# design.net
KiCad netlist of a schematic drawn in Altium Designer
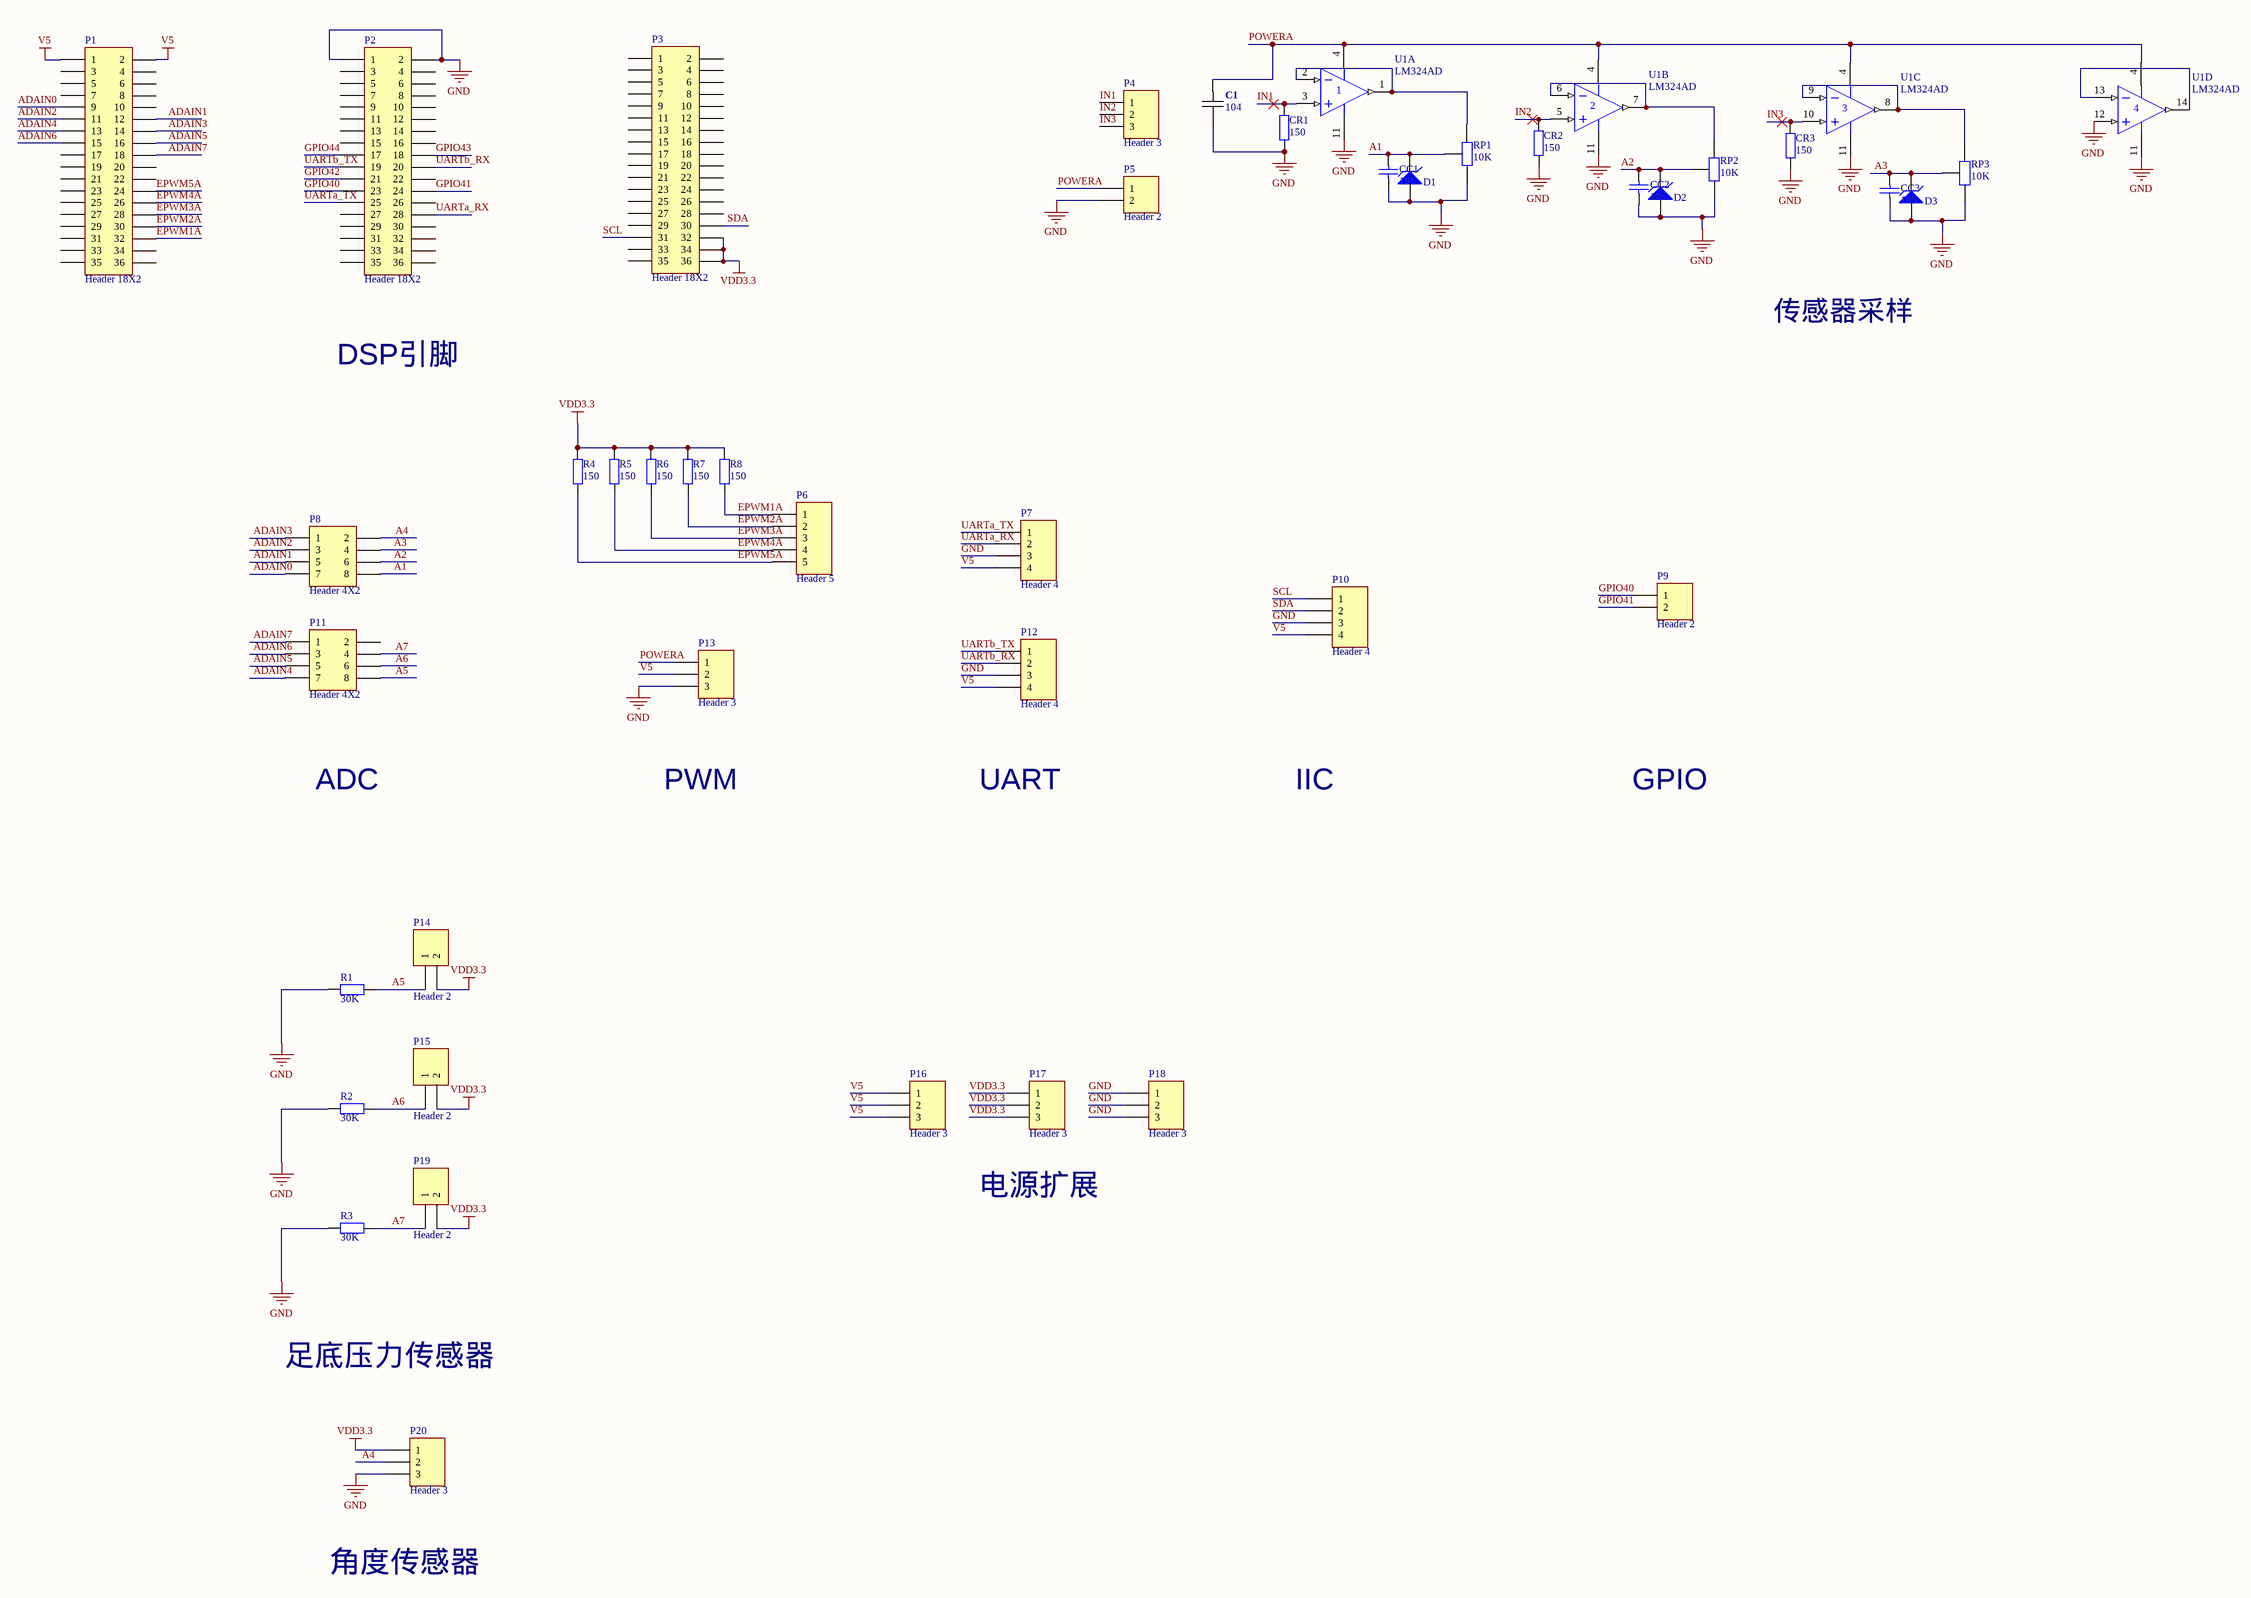
[diagram p0: 假肢控制电路.SchDoc]

(export (version "E")
  (design (tool "Eeschema 10.0.6"))
  (components
    (comp (ref "C1")
      (value "104")
      (footprint "LC-0805_C")
      (description "1.02.08.0014")
      (libsource (lib "电容(插装)") (part "CAP(瓷片,104)"))
    )
    (comp (ref "CC1")
      (value "105")
      (footprint "LC-0805_C")
      (description "Polarized Capacitor (Radial)")
      (fields (field (name "PUBLISHER") "Altium Limited"))
      (libsource (lib "主板") (part "Cap Chip 0805"))
    )
    (comp (ref "CC2")
      (value "105")
      (footprint "LC-0805_C")
      (description "Polarized Capacitor (Radial)")
      (fields (field (name "PUBLISHER") "Altium Limited"))
      (libsource (lib "主板") (part "Cap Chip 0805"))
    )
    (comp (ref "CC3")
      (value "105")
      (footprint "LC-0805_C")
      (description "Polarized Capacitor (Radial)")
      (fields (field (name "PUBLISHER") "Altium Limited"))
      (libsource (lib "主板") (part "Cap Chip 0805"))
    )
    (comp (ref "CR1")
      (value "150")
      (footprint "LC-0805_R")
      (description "Resistor")
      (fields (field (name "PUBLISHER") "Altium Limited"))
      (libsource (lib "主板") (part "Resistor Chip 0805"))
    )
    (comp (ref "CR2")
      (value "150")
      (footprint "LC-0805_R")
      (description "Resistor")
      (fields (field (name "PUBLISHER") "Altium Limited"))
      (libsource (lib "主板") (part "Resistor Chip 0805"))
    )
    (comp (ref "CR3")
      (value "150")
      (footprint "LC-0805_R")
      (description "Resistor")
      (fields (field (name "PUBLISHER") "Altium Limited"))
      (libsource (lib "主板") (part "Resistor Chip 0805"))
    )
    (comp (ref "D1")
      (value "Diode  Zener")
      (footprint "LC-1206")
      (description "Zener Diode")
      (fields (field (name "PUBLISHER") "Altium Limited"))
      (libsource (lib "EButterflyIntegratedLibrary") (part "Diode  Zener"))
    )
    (comp (ref "D2")
      (value "Diode  Zener")
      (footprint "LC-1206")
      (description "Zener Diode")
      (fields (field (name "PUBLISHER") "Altium Limited"))
      (libsource (lib "EButterflyIntegratedLibrary") (part "Diode  Zener"))
    )
    (comp (ref "D3")
      (value "Diode  Zener")
      (footprint "LC-1206")
      (description "Zener Diode")
      (fields (field (name "PUBLISHER") "Altium Limited"))
      (libsource (lib "EButterflyIntegratedLibrary") (part "Diode  Zener"))
    )
    (comp (ref "P1")
      (value "Header 18X2")
      (footprint "HDR2X18")
      (description "Header, 18-Pin, Dual row")
      (fields (field (name "PUBLISHER") "Altium Limited"))
      (libsource (lib "Miscellaneous Connectors") (part "Header 18X2"))
    )
    (comp (ref "P2")
      (value "Header 18X2")
      (footprint "HDR2X18")
      (description "Header, 18-Pin, Dual row")
      (fields (field (name "PUBLISHER") "Altium Limited"))
      (libsource (lib "Miscellaneous Connectors") (part "Header 18X2"))
    )
    (comp (ref "P3")
      (value "Header 18X2")
      (footprint "HDR2X18")
      (description "Header, 18-Pin, Dual row")
      (fields (field (name "PUBLISHER") "Altium Limited"))
      (libsource (lib "Miscellaneous Connectors") (part "Header 18X2"))
    )
    (comp (ref "P4")
      (value "Header 3")
      (footprint "XH2.54-3")
      (description "Header, 3-Pin")
      (fields (field (name "PUBLISHER") "Altium Limited"))
      (libsource (lib "Miscellaneous Connectors") (part "Header 3"))
    )
    (comp (ref "P5")
      (value "Header 2")
      (footprint "XH2.54-2")
      (description "Header, 2-Pin")
      (fields (field (name "PUBLISHER") "Altium Limited"))
      (libsource (lib "Miscellaneous Connectors") (part "Header 2"))
    )
    (comp (ref "P6")
      (value "Header 5")
      (footprint "XH2.54-LI-5P")
      (description "Header, 5-Pin")
      (fields (field (name "PUBLISHER") "Altium Limited"))
      (libsource (lib "Miscellaneous Connectors") (part "Header 5"))
    )
    (comp (ref "P7")
      (value "Header 4")
      (footprint "HDR1X4")
      (description "Header, 4-Pin")
      (fields (field (name "PUBLISHER") "Altium Limited"))
      (libsource (lib "Miscellaneous Connectors") (part "Header 4"))
    )
    (comp (ref "P8")
      (value "Header 4X2")
      (footprint "HDR2X4")
      (description "Header, 4-Pin, Dual row")
      (fields (field (name "PUBLISHER") "Altium Limited"))
      (libsource (lib "Miscellaneous Connectors") (part "Header 4X2"))
    )
    (comp (ref "P9")
      (value "Header 2")
      (footprint "HDR1X2")
      (description "Header, 2-Pin")
      (fields (field (name "PUBLISHER") "Altium Limited"))
      (libsource (lib "Miscellaneous Connectors") (part "Header 2"))
    )
    (comp (ref "P10")
      (value "Header 4")
      (footprint "KF接线端子:KF2EDGK5.0-LI-4P")
      (description "Header, 4-Pin")
      (fields (field (name "PUBLISHER") "Altium Limited"))
      (libsource (lib "Miscellaneous Connectors") (part "Header 4"))
    )
    (comp (ref "P11")
      (value "Header 4X2")
      (footprint "HDR2X4")
      (description "Header, 4-Pin, Dual row")
      (fields (field (name "PUBLISHER") "Altium Limited"))
      (libsource (lib "Miscellaneous Connectors") (part "Header 4X2"))
    )
    (comp (ref "P12")
      (value "Header 4")
      (footprint "HDR1X4")
      (description "Header, 4-Pin")
      (fields (field (name "PUBLISHER") "Altium Limited"))
      (libsource (lib "Miscellaneous Connectors") (part "Header 4"))
    )
    (comp (ref "P13")
      (value "Header 3")
      (footprint "XH2.54-LI-3P")
      (description "Header, 3-Pin")
      (fields (field (name "PUBLISHER") "Altium Limited"))
      (libsource (lib "Miscellaneous Connectors") (part "Header 3"))
    )
    (comp (ref "P14")
      (value "Header 2")
      (footprint "XH2.54-2")
      (description "Header, 2-Pin")
      (fields (field (name "PUBLISHER") "Altium Limited"))
      (libsource (lib "") (part "Header 2_1"))
    )
    (comp (ref "P15")
      (value "Header 2")
      (footprint "XH2.54-2")
      (description "Header, 2-Pin")
      (fields (field (name "PUBLISHER") "Altium Limited"))
      (libsource (lib "") (part "Header 2_1"))
    )
    (comp (ref "P16")
      (value "Header 3")
      (footprint "HDR1X3")
      (description "Header, 3-Pin")
      (fields (field (name "PUBLISHER") "Altium Limited"))
      (libsource (lib "Miscellaneous Connectors") (part "Header 3"))
    )
    (comp (ref "P17")
      (value "Header 3")
      (footprint "HDR1X3")
      (description "Header, 3-Pin")
      (fields (field (name "PUBLISHER") "Altium Limited"))
      (libsource (lib "Miscellaneous Connectors") (part "Header 3"))
    )
    (comp (ref "P18")
      (value "Header 3")
      (footprint "HDR1X3")
      (description "Header, 3-Pin")
      (fields (field (name "PUBLISHER") "Altium Limited"))
      (libsource (lib "Miscellaneous Connectors") (part "Header 3"))
    )
    (comp (ref "P19")
      (value "Header 2")
      (footprint "XH2.54-2")
      (description "Header, 2-Pin")
      (fields (field (name "PUBLISHER") "Altium Limited"))
      (libsource (lib "") (part "Header 2_1"))
    )
    (comp (ref "P20")
      (value "Header 3")
      (footprint "XH2.54-3")
      (description "Header, 3-Pin")
      (fields (field (name "PUBLISHER") "Altium Limited"))
      (libsource (lib "Miscellaneous Connectors") (part "Header 3"))
    )
    (comp (ref "R1")
      (value "30K")
      (footprint "LC-0805_R")
      (description "Resistor")
      (fields (field (name "Comment") "3.3K") (field (name "PUBLISHER") "Altium Limited"))
      (libsource (lib "PCB_Project1") (part "Res2"))
    )
    (comp (ref "R2")
      (value "30K")
      (footprint "LC-0805_R")
      (description "Resistor")
      (fields (field (name "Comment") "3.3K") (field (name "PUBLISHER") "Altium Limited"))
      (libsource (lib "PCB_Project1") (part "Res2"))
    )
    (comp (ref "R3")
      (value "30K")
      (footprint "LC-0805_R")
      (description "Resistor")
      (fields (field (name "Comment") "3.3K") (field (name "PUBLISHER") "Altium Limited"))
      (libsource (lib "PCB_Project1") (part "Res2"))
    )
    (comp (ref "R4")
      (value "150")
      (footprint "LC-0805_R")
      (description "Resistor")
      (fields (field (name "PUBLISHER") "Altium Limited"))
      (libsource (lib "主板") (part "Resistor Chip 0805"))
    )
    (comp (ref "R5")
      (value "150")
      (footprint "LC-0805_R")
      (description "Resistor")
      (fields (field (name "PUBLISHER") "Altium Limited"))
      (libsource (lib "主板") (part "Resistor Chip 0805"))
    )
    (comp (ref "R6")
      (value "150")
      (footprint "LC-0805_R")
      (description "Resistor")
      (fields (field (name "PUBLISHER") "Altium Limited"))
      (libsource (lib "主板") (part "Resistor Chip 0805"))
    )
    (comp (ref "R7")
      (value "150")
      (footprint "LC-0805_R")
      (description "Resistor")
      (fields (field (name "PUBLISHER") "Altium Limited"))
      (libsource (lib "主板") (part "Resistor Chip 0805"))
    )
    (comp (ref "R8")
      (value "150")
      (footprint "LC-0805_R")
      (description "Resistor")
      (fields (field (name "PUBLISHER") "Altium Limited"))
      (libsource (lib "主板") (part "Resistor Chip 0805"))
    )
    (comp (ref "RP1") (value "10K") (footprint "VR5") (libsource (lib "BTS7960大功率直流电机驱动") (part "Res_t")))
    (comp (ref "RP2") (value "10K") (footprint "VR5") (libsource (lib "BTS7960大功率直流电机驱动") (part "Res_t")))
    (comp (ref "RP3") (value "10K") (footprint "VR5") (libsource (lib "BTS7960大功率直流电机驱动") (part "Res_t")))
    (comp (ref "U1")
      (value "LM324AD")
      (footprint "SO-14")
      (description "Quadruple Operational Amplifier")
      (fields (field (name "PUBLISHER") "Altium Limited"))
      (libsource (lib "主板") (part "LM324AD"))
    )
  )
  (nets
    (net (code "1") (name "/A1") (class "Default")
      (node (ref "CC1") (pin "2") (pinfunction "2_2") (pintype "passive"))
      (node (ref "D1") (pin "2") (pinfunction "K_2") (pintype "passive"))
      (node (ref "P8") (pin "8") (pinfunction "8_8") (pintype "passive"))
      (node (ref "RP1") (pin "2") (pinfunction "2_2") (pintype "passive"))
    )
    (net (code "2") (name "/A2") (class "Default")
      (node (ref "CC2") (pin "2") (pinfunction "2_2") (pintype "passive"))
      (node (ref "D2") (pin "2") (pinfunction "K_2") (pintype "passive"))
      (node (ref "P8") (pin "6") (pinfunction "6_6") (pintype "passive"))
      (node (ref "RP2") (pin "2") (pinfunction "2_2") (pintype "passive"))
    )
    (net (code "3") (name "/A3") (class "Default")
      (node (ref "CC3") (pin "2") (pinfunction "2_2") (pintype "passive"))
      (node (ref "D3") (pin "2") (pinfunction "K_2") (pintype "passive"))
      (node (ref "P8") (pin "4") (pinfunction "4_4") (pintype "passive"))
      (node (ref "RP3") (pin "2") (pinfunction "2_2") (pintype "passive"))
    )
    (net (code "4") (name "/A4") (class "Default")
      (node (ref "P20") (pin "2") (pinfunction "2_2") (pintype "passive"))
      (node (ref "P8") (pin "2") (pinfunction "2_2") (pintype "passive"))
    )
    (net (code "5") (name "/A5") (class "Default")
      (node (ref "P11") (pin "8") (pinfunction "8_8") (pintype "passive"))
      (node (ref "P14") (pin "1") (pinfunction "1_1") (pintype "passive"))
      (node (ref "R1") (pin "1") (pinfunction "1_1") (pintype "passive"))
    )
    (net (code "6") (name "/A6") (class "Default")
      (node (ref "P11") (pin "6") (pinfunction "6_6") (pintype "passive"))
      (node (ref "P15") (pin "1") (pinfunction "1_1") (pintype "passive"))
      (node (ref "R2") (pin "1") (pinfunction "1_1") (pintype "passive"))
    )
    (net (code "7") (name "/A7") (class "Default")
      (node (ref "P11") (pin "4") (pinfunction "4_4") (pintype "passive"))
      (node (ref "P19") (pin "1") (pinfunction "1_1") (pintype "passive"))
      (node (ref "R3") (pin "1") (pinfunction "1_1") (pintype "passive"))
    )
    (net (code "8") (name "/ADAIN0") (class "Default")
      (node (ref "P1") (pin "9") (pinfunction "9_9") (pintype "passive"))
      (node (ref "P8") (pin "7") (pinfunction "7_7") (pintype "passive"))
    )
    (net (code "9") (name "/ADAIN1") (class "Default")
      (node (ref "P1") (pin "12") (pinfunction "12_12") (pintype "passive"))
      (node (ref "P8") (pin "5") (pinfunction "5_5") (pintype "passive"))
    )
    (net (code "10") (name "/ADAIN2") (class "Default")
      (node (ref "P1") (pin "11") (pinfunction "11_11") (pintype "passive"))
      (node (ref "P8") (pin "3") (pinfunction "3_3") (pintype "passive"))
    )
    (net (code "11") (name "/ADAIN3") (class "Default")
      (node (ref "P1") (pin "14") (pinfunction "14_14") (pintype "passive"))
      (node (ref "P8") (pin "1") (pinfunction "1_1") (pintype "passive"))
    )
    (net (code "12") (name "/ADAIN4") (class "Default")
      (node (ref "P1") (pin "13") (pinfunction "13_13") (pintype "passive"))
      (node (ref "P11") (pin "7") (pinfunction "7_7") (pintype "passive"))
    )
    (net (code "13") (name "/ADAIN5") (class "Default")
      (node (ref "P1") (pin "16") (pinfunction "16_16") (pintype "passive"))
      (node (ref "P11") (pin "5") (pinfunction "5_5") (pintype "passive"))
    )
    (net (code "14") (name "/ADAIN6") (class "Default")
      (node (ref "P1") (pin "15") (pinfunction "15_15") (pintype "passive"))
      (node (ref "P11") (pin "3") (pinfunction "3_3") (pintype "passive"))
    )
    (net (code "15") (name "/ADAIN7") (class "Default")
      (node (ref "P1") (pin "18") (pinfunction "18_18") (pintype "passive"))
      (node (ref "P11") (pin "1") (pinfunction "1_1") (pintype "passive"))
    )
    (net (code "16") (name "/EPWM1A") (class "Default")
      (node (ref "P1") (pin "32") (pinfunction "32_32") (pintype "passive"))
      (node (ref "P6") (pin "1") (pinfunction "1_1") (pintype "passive"))
      (node (ref "R8") (pin "2") (pinfunction "2_2") (pintype "passive"))
    )
    (net (code "17") (name "/EPWM2A") (class "Default")
      (node (ref "P1") (pin "30") (pinfunction "30_30") (pintype "passive"))
      (node (ref "P6") (pin "2") (pinfunction "2_2") (pintype "passive"))
      (node (ref "R7") (pin "2") (pinfunction "2_2") (pintype "passive"))
    )
    (net (code "18") (name "/EPWM3A") (class "Default")
      (node (ref "P1") (pin "28") (pinfunction "28_28") (pintype "passive"))
      (node (ref "P6") (pin "3") (pinfunction "3_3") (pintype "passive"))
      (node (ref "R6") (pin "2") (pinfunction "2_2") (pintype "passive"))
    )
    (net (code "19") (name "/EPWM4A") (class "Default")
      (node (ref "P1") (pin "26") (pinfunction "26_26") (pintype "passive"))
      (node (ref "P6") (pin "4") (pinfunction "4_4") (pintype "passive"))
      (node (ref "R5") (pin "2") (pinfunction "2_2") (pintype "passive"))
    )
    (net (code "20") (name "/EPWM5A") (class "Default")
      (node (ref "P1") (pin "24") (pinfunction "24_24") (pintype "passive"))
      (node (ref "P6") (pin "5") (pinfunction "5_5") (pintype "passive"))
      (node (ref "R4") (pin "2") (pinfunction "2_2") (pintype "passive"))
    )
    (net (code "21") (name "/GPIO40") (class "Default")
      (node (ref "P2") (pin "23") (pinfunction "23_23") (pintype "passive"))
      (node (ref "P9") (pin "1") (pinfunction "1_1") (pintype "passive"))
    )
    (net (code "22") (name "/GPIO41") (class "Default")
      (node (ref "P2") (pin "24") (pinfunction "24_24") (pintype "passive"))
      (node (ref "P9") (pin "2") (pinfunction "2_2") (pintype "passive"))
    )
    (net (code "23") (name "/GPIO42") (class "Default")
      (node (ref "P2") (pin "21") (pinfunction "21_21") (pintype "passive"))
    )
    (net (code "24") (name "/GPIO43") (class "Default")
      (node (ref "P2") (pin "18") (pinfunction "18_18") (pintype "passive"))
    )
    (net (code "25") (name "/GPIO44") (class "Default")
      (node (ref "P2") (pin "17") (pinfunction "17_17") (pintype "passive"))
    )
    (net (code "26") (name "/IN1") (class "Default")
      (node (ref "CR1") (pin "1") (pinfunction "1_1") (pintype "passive"))
      (node (ref "P4") (pin "1") (pinfunction "1_1") (pintype "passive"))
      (node (ref "U1") (pin "3") (pinfunction "IN+_3") (pintype "input"))
    )
    (net (code "27") (name "/IN2") (class "Default")
      (node (ref "CR2") (pin "1") (pinfunction "1_1") (pintype "passive"))
      (node (ref "P4") (pin "2") (pinfunction "2_2") (pintype "passive"))
      (node (ref "U1") (pin "5") (pinfunction "IN+_5") (pintype "input"))
    )
    (net (code "28") (name "/IN3") (class "Default")
      (node (ref "CR3") (pin "1") (pinfunction "1_1") (pintype "passive"))
      (node (ref "P4") (pin "3") (pinfunction "3_3") (pintype "passive"))
      (node (ref "U1") (pin "10") (pinfunction "IN+_10") (pintype "input"))
    )
    (net (code "29") (name "/POWERA") (class "Default")
      (node (ref "C1") (pin "1") (pinfunction "1_1") (pintype "passive"))
      (node (ref "P13") (pin "1") (pinfunction "1_1") (pintype "passive"))
      (node (ref "P5") (pin "1") (pinfunction "1_1") (pintype "passive"))
      (node (ref "U1") (pin "4") (pinfunction "V+_4") (pintype "power_in"))
    )
    (net (code "30") (name "/SCL") (class "Default")
      (node (ref "P10") (pin "1") (pinfunction "1_1") (pintype "passive"))
      (node (ref "P3") (pin "31") (pinfunction "31_31") (pintype "passive"))
    )
    (net (code "31") (name "/SDA") (class "Default")
      (node (ref "P10") (pin "2") (pinfunction "2_2") (pintype "passive"))
      (node (ref "P3") (pin "30") (pinfunction "30_30") (pintype "passive"))
    )
    (net (code "32") (name "/UARTa_RX") (class "Default")
      (node (ref "P2") (pin "28") (pinfunction "28_28") (pintype "passive"))
      (node (ref "P7") (pin "2") (pinfunction "2_2") (pintype "passive"))
    )
    (net (code "33") (name "/UARTa_TX") (class "Default")
      (node (ref "P2") (pin "25") (pinfunction "25_25") (pintype "passive"))
      (node (ref "P7") (pin "1") (pinfunction "1_1") (pintype "passive"))
    )
    (net (code "34") (name "/UARTb_RX") (class "Default")
      (node (ref "P12") (pin "2") (pinfunction "2_2") (pintype "passive"))
      (node (ref "P2") (pin "20") (pinfunction "20_20") (pintype "passive"))
    )
    (net (code "35") (name "/UARTb_TX") (class "Default")
      (node (ref "P12") (pin "1") (pinfunction "1_1") (pintype "passive"))
      (node (ref "P2") (pin "19") (pinfunction "19_19") (pintype "passive"))
    )
    (net (code "36") (name "GND") (class "Default")
      (node (ref "C1") (pin "2") (pinfunction "2_2") (pintype "passive"))
      (node (ref "CC1") (pin "1") (pinfunction "1_1") (pintype "passive"))
      (node (ref "CC2") (pin "1") (pinfunction "1_1") (pintype "passive"))
      (node (ref "CC3") (pin "1") (pinfunction "1_1") (pintype "passive"))
      (node (ref "CR1") (pin "2") (pinfunction "2_2") (pintype "passive"))
      (node (ref "CR2") (pin "2") (pinfunction "2_2") (pintype "passive"))
      (node (ref "CR3") (pin "2") (pinfunction "2_2") (pintype "passive"))
      (node (ref "D1") (pin "1") (pinfunction "A_1") (pintype "passive"))
      (node (ref "D2") (pin "1") (pinfunction "A_1") (pintype "passive"))
      (node (ref "D3") (pin "1") (pinfunction "A_1") (pintype "passive"))
      (node (ref "P10") (pin "3") (pinfunction "3_3") (pintype "passive"))
      (node (ref "P12") (pin "3") (pinfunction "3_3") (pintype "passive"))
      (node (ref "P13") (pin "3") (pinfunction "3_3") (pintype "passive"))
      (node (ref "P18") (pin "1") (pinfunction "1_1") (pintype "passive"))
      (node (ref "P18") (pin "2") (pinfunction "2_2") (pintype "passive"))
      (node (ref "P18") (pin "3") (pinfunction "3_3") (pintype "passive"))
      (node (ref "P2") (pin "1") (pinfunction "1_1") (pintype "passive"))
      (node (ref "P2") (pin "2") (pinfunction "2_2") (pintype "passive"))
      (node (ref "P20") (pin "3") (pinfunction "3_3") (pintype "passive"))
      (node (ref "P5") (pin "2") (pinfunction "2_2") (pintype "passive"))
      (node (ref "P7") (pin "3") (pinfunction "3_3") (pintype "passive"))
      (node (ref "R1") (pin "2") (pinfunction "2_2") (pintype "passive"))
      (node (ref "R2") (pin "2") (pinfunction "2_2") (pintype "passive"))
      (node (ref "R3") (pin "2") (pinfunction "2_2") (pintype "passive"))
      (node (ref "RP1") (pin "1") (pinfunction "1_1") (pintype "passive"))
      (node (ref "RP2") (pin "1") (pinfunction "1_1") (pintype "passive"))
      (node (ref "RP3") (pin "1") (pinfunction "1_1") (pintype "passive"))
      (node (ref "U1") (pin "11") (pinfunction "V-_11") (pintype "power_in"))
      (node (ref "U1") (pin "12") (pinfunction "IN+_12") (pintype "input"))
    )
    (net (code "37") (name "Net-(U1A-IN-)") (class "Default")
      (node (ref "RP1") (pin "3") (pinfunction "3_3") (pintype "passive"))
      (node (ref "U1") (pin "1") (pinfunction "OUT_1") (pintype "output"))
      (node (ref "U1") (pin "2") (pinfunction "IN-_2") (pintype "input"))
    )
    (net (code "38") (name "Net-(U1B-IN-)") (class "Default")
      (node (ref "RP2") (pin "3") (pinfunction "3_3") (pintype "passive"))
      (node (ref "U1") (pin "6") (pinfunction "IN-_6") (pintype "input"))
      (node (ref "U1") (pin "7") (pinfunction "OUT_7") (pintype "output"))
    )
    (net (code "39") (name "Net-(U1C-IN-)") (class "Default")
      (node (ref "RP3") (pin "3") (pinfunction "3_3") (pintype "passive"))
      (node (ref "U1") (pin "8") (pinfunction "OUT_8") (pintype "output"))
      (node (ref "U1") (pin "9") (pinfunction "IN-_9") (pintype "input"))
    )
    (net (code "40") (name "Net-(U1D-IN-)") (class "Default")
      (node (ref "U1") (pin "13") (pinfunction "IN-_13") (pintype "input"))
      (node (ref "U1") (pin "14") (pinfunction "OUT_14") (pintype "output"))
    )
    (net (code "41") (name "V5") (class "Default")
      (node (ref "P1") (pin "1") (pinfunction "1_1") (pintype "passive"))
      (node (ref "P1") (pin "2") (pinfunction "2_2") (pintype "passive"))
      (node (ref "P10") (pin "4") (pinfunction "4_4") (pintype "passive"))
      (node (ref "P12") (pin "4") (pinfunction "4_4") (pintype "passive"))
      (node (ref "P13") (pin "2") (pinfunction "2_2") (pintype "passive"))
      (node (ref "P16") (pin "1") (pinfunction "1_1") (pintype "passive"))
      (node (ref "P16") (pin "2") (pinfunction "2_2") (pintype "passive"))
      (node (ref "P16") (pin "3") (pinfunction "3_3") (pintype "passive"))
      (node (ref "P7") (pin "4") (pinfunction "4_4") (pintype "passive"))
    )
    (net (code "42") (name "VDD3.3") (class "Default")
      (node (ref "P14") (pin "2") (pinfunction "2_2") (pintype "passive"))
      (node (ref "P15") (pin "2") (pinfunction "2_2") (pintype "passive"))
      (node (ref "P17") (pin "1") (pinfunction "1_1") (pintype "passive"))
      (node (ref "P17") (pin "2") (pinfunction "2_2") (pintype "passive"))
      (node (ref "P17") (pin "3") (pinfunction "3_3") (pintype "passive"))
      (node (ref "P19") (pin "2") (pinfunction "2_2") (pintype "passive"))
      (node (ref "P20") (pin "1") (pinfunction "1_1") (pintype "passive"))
      (node (ref "P3") (pin "32") (pinfunction "32_32") (pintype "passive"))
      (node (ref "P3") (pin "34") (pinfunction "34_34") (pintype "passive"))
      (node (ref "P3") (pin "36") (pinfunction "36_36") (pintype "passive"))
      (node (ref "R4") (pin "1") (pinfunction "1_1") (pintype "passive"))
      (node (ref "R5") (pin "1") (pinfunction "1_1") (pintype "passive"))
      (node (ref "R6") (pin "1") (pinfunction "1_1") (pintype "passive"))
      (node (ref "R7") (pin "1") (pinfunction "1_1") (pintype "passive"))
      (node (ref "R8") (pin "1") (pinfunction "1_1") (pintype "passive"))
    )
    (net (code "43") (name "unconnected-(P1-Pad3)") (class "Default")
      (node (ref "P1") (pin "3") (pinfunction "3_3") (pintype "passive"))
    )
    (net (code "44") (name "unconnected-(P1-Pad4)") (class "Default")
      (node (ref "P1") (pin "4") (pinfunction "4_4") (pintype "passive"))
    )
    (net (code "45") (name "unconnected-(P1-Pad5)") (class "Default")
      (node (ref "P1") (pin "5") (pinfunction "5_5") (pintype "passive"))
    )
    (net (code "46") (name "unconnected-(P1-Pad6)") (class "Default")
      (node (ref "P1") (pin "6") (pinfunction "6_6") (pintype "passive"))
    )
    (net (code "47") (name "unconnected-(P1-Pad7)") (class "Default")
      (node (ref "P1") (pin "7") (pinfunction "7_7") (pintype "passive"))
    )
    (net (code "48") (name "unconnected-(P1-Pad8)") (class "Default")
      (node (ref "P1") (pin "8") (pinfunction "8_8") (pintype "passive"))
    )
    (net (code "49") (name "unconnected-(P1-Pad10)") (class "Default")
      (node (ref "P1") (pin "10") (pinfunction "10_10") (pintype "passive"))
    )
    (net (code "50") (name "unconnected-(P1-Pad17)") (class "Default")
      (node (ref "P1") (pin "17") (pinfunction "17_17") (pintype "passive"))
    )
    (net (code "51") (name "unconnected-(P1-Pad19)") (class "Default")
      (node (ref "P1") (pin "19") (pinfunction "19_19") (pintype "passive"))
    )
    (net (code "52") (name "unconnected-(P1-Pad20)") (class "Default")
      (node (ref "P1") (pin "20") (pinfunction "20_20") (pintype "passive"))
    )
    (net (code "53") (name "unconnected-(P1-Pad21)") (class "Default")
      (node (ref "P1") (pin "21") (pinfunction "21_21") (pintype "passive"))
    )
    (net (code "54") (name "unconnected-(P1-Pad22)") (class "Default")
      (node (ref "P1") (pin "22") (pinfunction "22_22") (pintype "passive"))
    )
    (net (code "55") (name "unconnected-(P1-Pad23)") (class "Default")
      (node (ref "P1") (pin "23") (pinfunction "23_23") (pintype "passive"))
    )
    (net (code "56") (name "unconnected-(P1-Pad25)") (class "Default")
      (node (ref "P1") (pin "25") (pinfunction "25_25") (pintype "passive"))
    )
    (net (code "57") (name "unconnected-(P1-Pad27)") (class "Default")
      (node (ref "P1") (pin "27") (pinfunction "27_27") (pintype "passive"))
    )
    (net (code "58") (name "unconnected-(P1-Pad29)") (class "Default")
      (node (ref "P1") (pin "29") (pinfunction "29_29") (pintype "passive"))
    )
    (net (code "59") (name "unconnected-(P1-Pad31)") (class "Default")
      (node (ref "P1") (pin "31") (pinfunction "31_31") (pintype "passive"))
    )
    (net (code "60") (name "unconnected-(P1-Pad33)") (class "Default")
      (node (ref "P1") (pin "33") (pinfunction "33_33") (pintype "passive"))
    )
    (net (code "61") (name "unconnected-(P1-Pad34)") (class "Default")
      (node (ref "P1") (pin "34") (pinfunction "34_34") (pintype "passive"))
    )
    (net (code "62") (name "unconnected-(P1-Pad35)") (class "Default")
      (node (ref "P1") (pin "35") (pinfunction "35_35") (pintype "passive"))
    )
    (net (code "63") (name "unconnected-(P1-Pad36)") (class "Default")
      (node (ref "P1") (pin "36") (pinfunction "36_36") (pintype "passive"))
    )
    (net (code "64") (name "unconnected-(P2-Pad3)") (class "Default")
      (node (ref "P2") (pin "3") (pinfunction "3_3") (pintype "passive"))
    )
    (net (code "65") (name "unconnected-(P2-Pad4)") (class "Default")
      (node (ref "P2") (pin "4") (pinfunction "4_4") (pintype "passive"))
    )
    (net (code "66") (name "unconnected-(P2-Pad5)") (class "Default")
      (node (ref "P2") (pin "5") (pinfunction "5_5") (pintype "passive"))
    )
    (net (code "67") (name "unconnected-(P2-Pad6)") (class "Default")
      (node (ref "P2") (pin "6") (pinfunction "6_6") (pintype "passive"))
    )
    (net (code "68") (name "unconnected-(P2-Pad7)") (class "Default")
      (node (ref "P2") (pin "7") (pinfunction "7_7") (pintype "passive"))
    )
    (net (code "69") (name "unconnected-(P2-Pad8)") (class "Default")
      (node (ref "P2") (pin "8") (pinfunction "8_8") (pintype "passive"))
    )
    (net (code "70") (name "unconnected-(P2-Pad9)") (class "Default")
      (node (ref "P2") (pin "9") (pinfunction "9_9") (pintype "passive"))
    )
    (net (code "71") (name "unconnected-(P2-Pad10)") (class "Default")
      (node (ref "P2") (pin "10") (pinfunction "10_10") (pintype "passive"))
    )
    (net (code "72") (name "unconnected-(P2-Pad11)") (class "Default")
      (node (ref "P2") (pin "11") (pinfunction "11_11") (pintype "passive"))
    )
    (net (code "73") (name "unconnected-(P2-Pad12)") (class "Default")
      (node (ref "P2") (pin "12") (pinfunction "12_12") (pintype "passive"))
    )
    (net (code "74") (name "unconnected-(P2-Pad13)") (class "Default")
      (node (ref "P2") (pin "13") (pinfunction "13_13") (pintype "passive"))
    )
    (net (code "75") (name "unconnected-(P2-Pad14)") (class "Default")
      (node (ref "P2") (pin "14") (pinfunction "14_14") (pintype "passive"))
    )
    (net (code "76") (name "unconnected-(P2-Pad15)") (class "Default")
      (node (ref "P2") (pin "15") (pinfunction "15_15") (pintype "passive"))
    )
    (net (code "77") (name "unconnected-(P2-Pad16)") (class "Default")
      (node (ref "P2") (pin "16") (pinfunction "16_16") (pintype "passive"))
    )
    (net (code "78") (name "unconnected-(P2-Pad22)") (class "Default")
      (node (ref "P2") (pin "22") (pinfunction "22_22") (pintype "passive"))
    )
    (net (code "79") (name "unconnected-(P2-Pad26)") (class "Default")
      (node (ref "P2") (pin "26") (pinfunction "26_26") (pintype "passive"))
    )
    (net (code "80") (name "unconnected-(P2-Pad27)") (class "Default")
      (node (ref "P2") (pin "27") (pinfunction "27_27") (pintype "passive"))
    )
    (net (code "81") (name "unconnected-(P2-Pad29)") (class "Default")
      (node (ref "P2") (pin "29") (pinfunction "29_29") (pintype "passive"))
    )
    (net (code "82") (name "unconnected-(P2-Pad30)") (class "Default")
      (node (ref "P2") (pin "30") (pinfunction "30_30") (pintype "passive"))
    )
    (net (code "83") (name "unconnected-(P2-Pad31)") (class "Default")
      (node (ref "P2") (pin "31") (pinfunction "31_31") (pintype "passive"))
    )
    (net (code "84") (name "unconnected-(P2-Pad32)") (class "Default")
      (node (ref "P2") (pin "32") (pinfunction "32_32") (pintype "passive"))
    )
    (net (code "85") (name "unconnected-(P2-Pad33)") (class "Default")
      (node (ref "P2") (pin "33") (pinfunction "33_33") (pintype "passive"))
    )
    (net (code "86") (name "unconnected-(P2-Pad34)") (class "Default")
      (node (ref "P2") (pin "34") (pinfunction "34_34") (pintype "passive"))
    )
    (net (code "87") (name "unconnected-(P2-Pad35)") (class "Default")
      (node (ref "P2") (pin "35") (pinfunction "35_35") (pintype "passive"))
    )
    (net (code "88") (name "unconnected-(P2-Pad36)") (class "Default")
      (node (ref "P2") (pin "36") (pinfunction "36_36") (pintype "passive"))
    )
    (net (code "89") (name "unconnected-(P3-Pad1)") (class "Default")
      (node (ref "P3") (pin "1") (pinfunction "1_1") (pintype "passive"))
    )
    (net (code "90") (name "unconnected-(P3-Pad2)") (class "Default")
      (node (ref "P3") (pin "2") (pinfunction "2_2") (pintype "passive"))
    )
    (net (code "91") (name "unconnected-(P3-Pad3)") (class "Default")
      (node (ref "P3") (pin "3") (pinfunction "3_3") (pintype "passive"))
    )
    (net (code "92") (name "unconnected-(P3-Pad4)") (class "Default")
      (node (ref "P3") (pin "4") (pinfunction "4_4") (pintype "passive"))
    )
    (net (code "93") (name "unconnected-(P3-Pad5)") (class "Default")
      (node (ref "P3") (pin "5") (pinfunction "5_5") (pintype "passive"))
    )
    (net (code "94") (name "unconnected-(P3-Pad6)") (class "Default")
      (node (ref "P3") (pin "6") (pinfunction "6_6") (pintype "passive"))
    )
    (net (code "95") (name "unconnected-(P3-Pad7)") (class "Default")
      (node (ref "P3") (pin "7") (pinfunction "7_7") (pintype "passive"))
    )
    (net (code "96") (name "unconnected-(P3-Pad8)") (class "Default")
      (node (ref "P3") (pin "8") (pinfunction "8_8") (pintype "passive"))
    )
    (net (code "97") (name "unconnected-(P3-Pad9)") (class "Default")
      (node (ref "P3") (pin "9") (pinfunction "9_9") (pintype "passive"))
    )
    (net (code "98") (name "unconnected-(P3-Pad10)") (class "Default")
      (node (ref "P3") (pin "10") (pinfunction "10_10") (pintype "passive"))
    )
    (net (code "99") (name "unconnected-(P3-Pad11)") (class "Default")
      (node (ref "P3") (pin "11") (pinfunction "11_11") (pintype "passive"))
    )
    (net (code "100") (name "unconnected-(P3-Pad12)") (class "Default")
      (node (ref "P3") (pin "12") (pinfunction "12_12") (pintype "passive"))
    )
    (net (code "101") (name "unconnected-(P3-Pad13)") (class "Default")
      (node (ref "P3") (pin "13") (pinfunction "13_13") (pintype "passive"))
    )
    (net (code "102") (name "unconnected-(P3-Pad14)") (class "Default")
      (node (ref "P3") (pin "14") (pinfunction "14_14") (pintype "passive"))
    )
    (net (code "103") (name "unconnected-(P3-Pad15)") (class "Default")
      (node (ref "P3") (pin "15") (pinfunction "15_15") (pintype "passive"))
    )
    (net (code "104") (name "unconnected-(P3-Pad16)") (class "Default")
      (node (ref "P3") (pin "16") (pinfunction "16_16") (pintype "passive"))
    )
    (net (code "105") (name "unconnected-(P3-Pad17)") (class "Default")
      (node (ref "P3") (pin "17") (pinfunction "17_17") (pintype "passive"))
    )
    (net (code "106") (name "unconnected-(P3-Pad18)") (class "Default")
      (node (ref "P3") (pin "18") (pinfunction "18_18") (pintype "passive"))
    )
    (net (code "107") (name "unconnected-(P3-Pad19)") (class "Default")
      (node (ref "P3") (pin "19") (pinfunction "19_19") (pintype "passive"))
    )
    (net (code "108") (name "unconnected-(P3-Pad20)") (class "Default")
      (node (ref "P3") (pin "20") (pinfunction "20_20") (pintype "passive"))
    )
    (net (code "109") (name "unconnected-(P3-Pad21)") (class "Default")
      (node (ref "P3") (pin "21") (pinfunction "21_21") (pintype "passive"))
    )
    (net (code "110") (name "unconnected-(P3-Pad22)") (class "Default")
      (node (ref "P3") (pin "22") (pinfunction "22_22") (pintype "passive"))
    )
    (net (code "111") (name "unconnected-(P3-Pad23)") (class "Default")
      (node (ref "P3") (pin "23") (pinfunction "23_23") (pintype "passive"))
    )
    (net (code "112") (name "unconnected-(P3-Pad24)") (class "Default")
      (node (ref "P3") (pin "24") (pinfunction "24_24") (pintype "passive"))
    )
    (net (code "113") (name "unconnected-(P3-Pad25)") (class "Default")
      (node (ref "P3") (pin "25") (pinfunction "25_25") (pintype "passive"))
    )
    (net (code "114") (name "unconnected-(P3-Pad26)") (class "Default")
      (node (ref "P3") (pin "26") (pinfunction "26_26") (pintype "passive"))
    )
    (net (code "115") (name "unconnected-(P3-Pad27)") (class "Default")
      (node (ref "P3") (pin "27") (pinfunction "27_27") (pintype "passive"))
    )
    (net (code "116") (name "unconnected-(P3-Pad28)") (class "Default")
      (node (ref "P3") (pin "28") (pinfunction "28_28") (pintype "passive"))
    )
    (net (code "117") (name "unconnected-(P3-Pad29)") (class "Default")
      (node (ref "P3") (pin "29") (pinfunction "29_29") (pintype "passive"))
    )
    (net (code "118") (name "unconnected-(P3-Pad33)") (class "Default")
      (node (ref "P3") (pin "33") (pinfunction "33_33") (pintype "passive"))
    )
    (net (code "119") (name "unconnected-(P3-Pad35)") (class "Default")
      (node (ref "P3") (pin "35") (pinfunction "35_35") (pintype "passive"))
    )
    (net (code "120") (name "unconnected-(P11-Pad2)") (class "Default")
      (node (ref "P11") (pin "2") (pinfunction "2_2") (pintype "passive"))
    )
  )
)
